# Booster_PA_PREAMP.net
KiCad netlist of a schematic drawn in Altium Designer
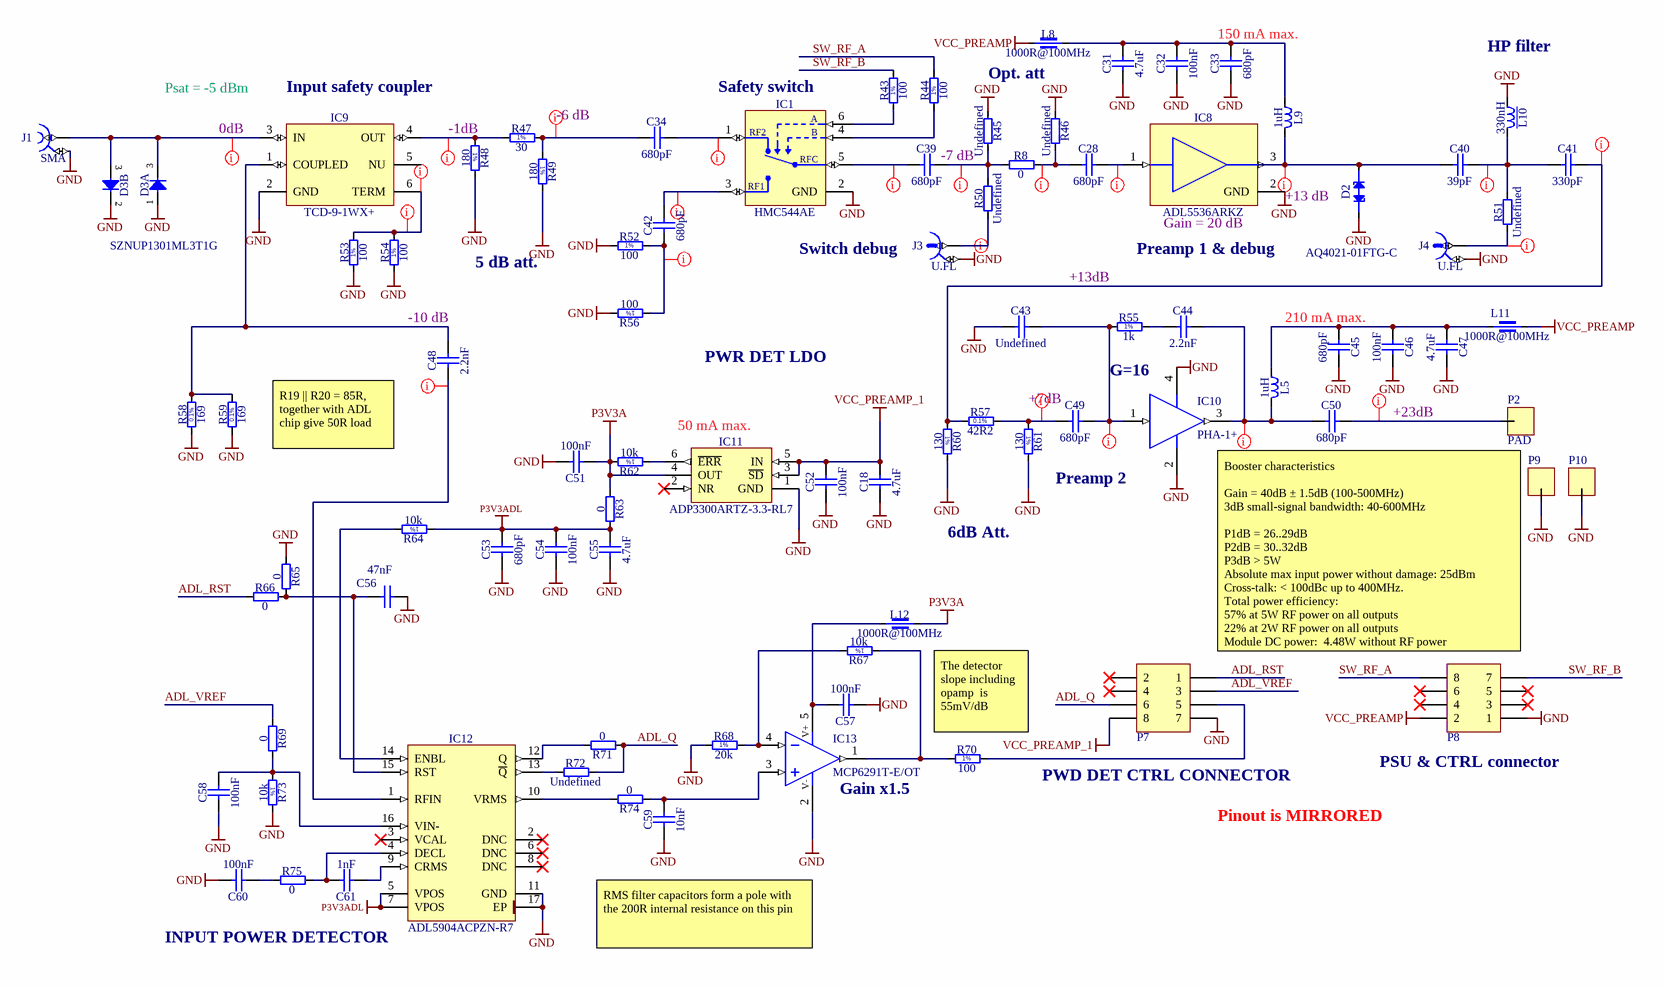
[diagram p0: Booster_PA_PREAMP.SchDoc]

(export (version "E")
  (design (tool "Eeschema 10.0.6"))
  (components
    (comp (ref "C18")
      (value "4.7uF")
      (footprint "CAPC1709X95N")
      (description "Non-polarised capacitor")
      (fields
        (field (name "MANUFACTURER") "GENERIC")
        (field (name "MANUFACTURER PART NUMBER") "CC0603_4.7UF_16V_10%_X5R")
        (field (name "AUTHOR") "CERN DEM JLC")
      )
      (libsource (lib "Capacitors") (part "Capacitor - non polarized"))
    )
    (comp (ref "C28")
      (value "680pF")
      (footprint "CAPC1608X87N")
      (description "Non-polarised capacitor")
      (fields
        (field (name "PART NUMBER") "CC0603_680PF_50V_5%_NP0")
        (field (name "VOLTAGE") "50V")
        (field (name "AUTHOR") "CERN DEM JLC")
      )
      (libsource (lib "Capacitors") (part "Capacitor - non polarized"))
    )
    (comp (ref "C31")
      (value "4.7uF")
      (footprint "CAPC1709X95N")
      (description "Non-polarised capacitor")
      (fields
        (field (name "MANUFACTURER") "GENERIC")
        (field (name "MANUFACTURER PART NUMBER") "CC0603_4.7UF_16V_10%_X5R")
        (field (name "AUTHOR") "CERN DEM JLC")
      )
      (libsource (lib "Capacitors") (part "Capacitor - non polarized"))
    )
    (comp (ref "C32")
      (value "100nF")
      (footprint "CAPC1608X87N")
      (description "Non-polarised capacitor")
      (fields
        (field (name "MANUFACTURER") "GENERIC")
        (field (name "MANUFACTURER PART NUMBER") "CC0603_100NF_50V_10%_X7R")
        (field (name "AUTHOR") "CERN DEM JLC")
      )
      (libsource (lib "Capacitors") (part "Capacitor - non polarized"))
    )
    (comp (ref "C33")
      (value "680pF")
      (footprint "CAPC1608X87N")
      (description "Non-polarised capacitor")
      (fields
        (field (name "PART NUMBER") "CC0603_680PF_50V_5%_NP0")
        (field (name "VOLTAGE") "50V")
        (field (name "AUTHOR") "CERN DEM JLC")
      )
      (libsource (lib "Capacitors") (part "Capacitor - non polarized"))
    )
    (comp (ref "C34")
      (value "680pF")
      (footprint "CAPC1608X87N")
      (description "Non-polarised capacitor")
      (fields
        (field (name "PART NUMBER") "CC0603_680PF_50V_5%_NP0")
        (field (name "VOLTAGE") "50V")
        (field (name "AUTHOR") "CERN DEM JLC")
      )
      (libsource (lib "Capacitors") (part "Capacitor - non polarized"))
    )
    (comp (ref "C39")
      (value "680pF")
      (footprint "CAPC1608X87N")
      (description "Non-polarised capacitor")
      (fields
        (field (name "PART NUMBER") "CC0603_680PF_50V_5%_NP0")
        (field (name "VOLTAGE") "50V")
        (field (name "AUTHOR") "CERN DEM JLC")
      )
      (libsource (lib "Capacitors") (part "Capacitor - non polarized"))
    )
    (comp (ref "C40")
      (value "39pF")
      (footprint "CAPC1608X87N")
      (description "Non-polarised capacitor")
      (fields
        (field (name "PART NUMBER") "CC0603_39PF_100V_1%_NP0")
        (field (name "VOLTAGE") "100V")
        (field (name "AUTHOR") "GK")
      )
      (libsource (lib "Passives_RC") (part "CC0603_39PF_50V_1%_NP0"))
    )
    (comp (ref "C41")
      (value "330pF")
      (footprint "CAPC1608X87N")
      (description "Non-polarised capacitor")
      (fields
        (field (name "MANUFACTURER") "GENERIC")
        (field (name "MANUFACTURER PART NUMBER") "CC0603_330PF_50V_1%_NP0")
        (field (name "AUTHOR") "CERN DEM MR")
      )
      (libsource (lib "Capacitors") (part "Capacitor - non polarized"))
    )
    (comp (ref "C42")
      (value "680pF")
      (footprint "CAPC1608X87N")
      (description "Non-polarised capacitor")
      (fields
        (field (name "PART NUMBER") "CC0603_680PF_50V_5%_NP0")
        (field (name "VOLTAGE") "50V")
        (field (name "AUTHOR") "CERN DEM JLC")
      )
      (libsource (lib "Capacitors") (part "Capacitor - non polarized"))
    )
    (comp (ref "C43")
      (value "Undefined")
      (footprint "CAPC1608X90N")
      (description "Non-polarised capacitor")
      (fields (field (name "PART NUMBER") "CC0603_NO-VALUE") (field (name "AUTHOR") "CERN DEM MR"))
      (libsource (lib "Capacitors") (part "Capacitor - non polarized"))
    )
    (comp (ref "C44")
      (value "2.2nF")
      (footprint "CAPC1608X87N")
      (description "Non-polarised capacitor")
      (fields
        (field (name "PART NUMBER") "CC0603_2.2NF_50V_5%_C0G")
        (field (name "VOLTAGE") "50V")
        (field (name "AUTHOR") "CERN DEM JMW")
      )
      (libsource (lib "Capacitors") (part "Capacitor - non polarized"))
    )
    (comp (ref "C45")
      (value "680pF")
      (footprint "CAPC1608X87N")
      (description "Non-polarised capacitor")
      (fields
        (field (name "MANUFACTURER") "GENERIC")
        (field (name "MANUFACTURER PART NUMBER") "CC0603_680PF_50V_5%_NP0")
        (field (name "AUTHOR") "CERN DEM JLC")
      )
      (libsource (lib "Capacitors") (part "Capacitor - non polarized"))
    )
    (comp (ref "C46")
      (value "100nF")
      (footprint "CAPC1608X87N")
      (description "Non-polarised capacitor")
      (fields
        (field (name "MANUFACTURER") "GENERIC")
        (field (name "MANUFACTURER PART NUMBER") "CC0603_100NF_50V_10%_X7R")
        (field (name "AUTHOR") "CERN DEM JLC")
      )
      (libsource (lib "Capacitors") (part "Capacitor - non polarized"))
    )
    (comp (ref "C47")
      (value "4.7uF")
      (footprint "CAPC1709X95N")
      (description "Non-polarised capacitor")
      (fields
        (field (name "MANUFACTURER") "GENERIC")
        (field (name "MANUFACTURER PART NUMBER") "CC0603_4.7UF_16V_10%_X5R")
        (field (name "AUTHOR") "CERN DEM JLC")
      )
      (libsource (lib "Capacitors") (part "Capacitor - non polarized"))
    )
    (comp (ref "C48")
      (value "2.2nF")
      (footprint "CAPC1608X87N")
      (description "Non-polarised capacitor")
      (fields
        (field (name "PART NUMBER") "CC0603_2.2NF_50V_5%_C0G")
        (field (name "VOLTAGE") "50V")
        (field (name "AUTHOR") "CERN DEM JMW")
      )
      (libsource (lib "Capacitors") (part "Capacitor - non polarized"))
    )
    (comp (ref "C49")
      (value "680pF")
      (footprint "CAPC1608X87N")
      (description "Non-polarised capacitor")
      (fields
        (field (name "MANUFACTURER") "GENERIC")
        (field (name "MANUFACTURER PART NUMBER") "CC0603_680PF_50V_5%_NP0")
        (field (name "AUTHOR") "CERN DEM JLC")
      )
      (libsource (lib "Capacitors") (part "Capacitor - non polarized"))
    )
    (comp (ref "C50")
      (value "680pF")
      (footprint "CAPC1608X87N")
      (description "Non-polarised capacitor")
      (fields
        (field (name "MANUFACTURER") "GENERIC")
        (field (name "MANUFACTURER PART NUMBER") "CC0603_680PF_50V_5%_NP0")
        (field (name "AUTHOR") "CERN DEM JLC")
      )
      (libsource (lib "Capacitors") (part "Capacitor - non polarized"))
    )
    (comp (ref "C51")
      (value "100nF")
      (footprint "CAPC1608X87N")
      (description "Non-polarised capacitor")
      (fields
        (field (name "MANUFACTURER") "GENERIC")
        (field (name "MANUFACTURER PART NUMBER") "CC0603_100NF_50V_10%_X7R")
        (field (name "AUTHOR") "CERN DEM JLC")
      )
      (libsource (lib "Capacitors") (part "Capacitor - non polarized"))
    )
    (comp (ref "C52")
      (value "100nF")
      (footprint "CAPC1608X87N")
      (description "Non-polarised capacitor")
      (fields
        (field (name "MANUFACTURER") "GENERIC")
        (field (name "MANUFACTURER PART NUMBER") "CC0603_100NF_50V_10%_X7R")
        (field (name "AUTHOR") "CERN DEM JLC")
      )
      (libsource (lib "Capacitors") (part "Capacitor - non polarized"))
    )
    (comp (ref "C53")
      (value "680pF")
      (footprint "CAPC1608X87N")
      (description "Non-polarised capacitor")
      (fields
        (field (name "MANUFACTURER") "GENERIC")
        (field (name "MANUFACTURER PART NUMBER") "CC0603_680PF_50V_5%_NP0")
        (field (name "AUTHOR") "CERN DEM JLC")
      )
      (libsource (lib "Capacitors") (part "Capacitor - non polarized"))
    )
    (comp (ref "C54")
      (value "100nF")
      (footprint "CAPC1608X87N")
      (description "Non-polarised capacitor")
      (fields
        (field (name "MANUFACTURER") "GENERIC")
        (field (name "MANUFACTURER PART NUMBER") "CC0603_100NF_50V_10%_X7R")
        (field (name "AUTHOR") "CERN DEM JLC")
      )
      (libsource (lib "Capacitors") (part "Capacitor - non polarized"))
    )
    (comp (ref "C55")
      (value "4.7uF")
      (footprint "CAPC1709X95N")
      (description "Non-polarised capacitor")
      (fields
        (field (name "MANUFACTURER") "GENERIC")
        (field (name "MANUFACTURER PART NUMBER") "CC0603_4.7UF_16V_10%_X5R")
        (field (name "AUTHOR") "CERN DEM JLC")
      )
      (libsource (lib "Capacitors") (part "Capacitor - non polarized"))
    )
    (comp (ref "C56")
      (value "47nF")
      (footprint "CAPC1608X87N")
      (description "Non-polarised capacitor")
      (fields
        (field (name "PART NUMBER") "CC0603_47NF_25V_10%_X7R")
        (field (name "VOLTAGE") "25V")
        (field (name "AUTHOR") "CERN DEM JLC")
      )
      (libsource (lib "Capacitors") (part "Capacitor - non polarized"))
    )
    (comp (ref "C57")
      (value "100nF")
      (footprint "CAPC1608X87N")
      (description "Non-polarised capacitor")
      (fields
        (field (name "MANUFACTURER") "GENERIC")
        (field (name "MANUFACTURER PART NUMBER") "CC0603_100NF_50V_10%_X7R")
        (field (name "AUTHOR") "CERN DEM JLC")
      )
      (libsource (lib "Capacitors") (part "Capacitor - non polarized"))
    )
    (comp (ref "C58")
      (value "100nF")
      (footprint "CAPC1608X87N")
      (description "Non-polarised capacitor")
      (fields
        (field (name "MANUFACTURER") "GENERIC")
        (field (name "MANUFACTURER PART NUMBER") "CC0603_100NF_50V_10%_X7R")
        (field (name "AUTHOR") "CERN DEM JLC")
      )
      (libsource (lib "Capacitors") (part "Capacitor - non polarized"))
    )
    (comp (ref "C59")
      (value "10nF")
      (footprint "CAPC1005X55N")
      (description "Non-polarised capacitor")
      (fields
        (field (name "MANUFACTURER") "GENERIC")
        (field (name "MANUFACTURER PART NUMBER") "CC0402_10NF_25V_10%_X7R")
        (field (name "AUTHOR") "CERN DEM JLC")
      )
      (libsource (lib "Capacitors") (part "Capacitor - non polarized"))
    )
    (comp (ref "C60")
      (value "100nF")
      (footprint "CAPC1608X87N")
      (description "Non-polarised capacitor")
      (fields
        (field (name "MANUFACTURER") "GENERIC")
        (field (name "MANUFACTURER PART NUMBER") "CC0603_100NF_50V_10%_X7R")
        (field (name "AUTHOR") "CERN DEM JLC")
      )
      (libsource (lib "Capacitors") (part "Capacitor - non polarized"))
    )
    (comp (ref "C61")
      (value "1nF")
      (footprint "CAPC1005X55N")
      (description "Non-polarised capacitor")
      (fields
        (field (name "PART NUMBER") "CC0402_1NF_50V_10%_X7R")
        (field (name "VOLTAGE") "50V")
        (field (name "AUTHOR") "CERN DEM JLC")
      )
      (libsource (lib "Capacitors") (part "Capacitor - non polarized"))
    )
    (comp (ref "D2")
      (value "AQ4021-01FTG-C")
      (footprint "SOD2513X114N")
      (description "6V Bi-directional,ESD Protection for Transient Voltage Suppressor Diode")
      (fields (field (name "VOLTAGE") "6V") (field (name "POWER") "450W") (field (name "AUTHOR") "GK"))
      (libsource (lib "Diodes") (part "D_TVS_AQ4021-01FTG-C"))
    )
    (comp (ref "D3")
      (value "SZNUP1301ML3T1G")
      (footprint "SOT95P240X110-3N")
      (description "Low Capacitance Diode Array for ESD Protection in a Single Data Line")
      (fields (field (name "VOLTAGE") "70V") (field (name "POWER") "215mA") (field (name "AUTHOR") "GK"))
      (libsource (lib "Diodes") (part "D_TVS_SZNUP1301ML3T1G"))
    )
    (comp (ref "IC1")
      (value "HMC544AE")
      (footprint "SOT95P280X145-6N")
      (description "GaAs MMIC T/R Switch DC - 4 GHz")
      (fields (field (name "MANUFACTURER") "ANALOG DEVICES") (field (name "AUTHOR") "CERN DEM MR"))
      (libsource (lib "ICs And Semiconductors") (part "HMC544AE"))
    )
    (comp (ref "IC8")
      (value "ADL5536ARKZ")
      (footprint "ANALOG-DEVICES_SOT-89(RK-3)")
      (description "20MHz to 1GHz IF Gain Block")
      (fields (field (name "MANUFACTURER") "ANALOG DEVICES") (field (name "AUTHOR") "CERN DEM BC"))
      (libsource (lib "ICs And Semiconductors") (part "ADL5536"))
    )
    (comp (ref "IC9")
      (value "TCD-9-1WX+")
      (footprint "MINI-CIRCUITS_DB1627")
      (description "50 Ohm, 5 To 2000MHz, Directional Coupler")
      (fields (field (name "MANUFACTURER") "MINI-CIRCUITS") (field (name "AUTHOR") "CERN DEM BC"))
      (libsource (lib "ICs And Semiconductors") (part "TCD-9-1W"))
    )
    (comp (ref "IC10")
      (value "PHA-1+")
      (footprint "MINI-CIRCUITS_DF782")
      (description "Monolithic Amplifier")
      (fields (field (name "MANUFACTURER") "MINI-CIRCUITS") (field (name "AUTHOR") "CERN DEM BC"))
      (libsource (lib "ICs And Semiconductors") (part "Monolithic Amplifier Type 1"))
    )
    (comp (ref "IC11")
      (value "ADP3300ARTZ-3.3-RL7")
      (footprint "SOT95P280X145-6N")
      (description "High Accuracy anyCAP® 50 mA Low Dropout Linear Regulator")
      (fields (field (name "MANUFACTURER") "ANALOG DEVICES") (field (name "AUTHOR") "CERN DEM JLC"))
      (libsource (lib "ICs And Semiconductors") (part "ADP3300ARTZ"))
    )
    (comp (ref "IC12")
      (value "ADL5904ACPZN-R7")
      (footprint "QFN50P300X300X80-17N-S175")
      (description "DC to 6 GHz, 45 dB TruPwr Detector With Envelope Threshold Detection")
      (fields (field (name "MANUFACTURER") "ANALOG DEVICES") (field (name "AUTHOR") "CERN DEM MR"))
      (libsource (lib "ICs And Semiconductors") (part "ADL5904"))
    )
    (comp (ref "IC13")
      (value "MCP6291T-E/OT")
      (footprint "SOT95P270X145-5N")
      (description "Operational Amplifier")
      (fields (field (name "MANUFACTURER") "MICROCHIP TECHNOLOGY") (field (name "AUTHOR") "CERN DEM BC"))
      (libsource (lib "ICs And Semiconductors") (part "Operational Amplifier Type7"))
    )
    (comp (ref "J1")
      (value "SMA")
      (footprint "LINK_CONSMA002-SMD-G")
      (fields
        (field (name "PART NUMBER") "LINK_CONSMA002-SMD-G")
        (field (name "MANUFACTURER") "LINK TECHNOLOGIES")
        (field (name "MANUFACTURER PART NUMBER") "CONSMA002-SMD-G")
        (field (name "AUTHOR") "CERN DEM BC")
      )
      (libsource (lib "Connectors") (part "Coax_1Female_1Shield"))
    )
    (comp (ref "J3")
      (value "U.FL")
      (footprint "HIROSE_U.FL-R-SMT-1(10)")
      (fields
        (field (name "PART NUMBER") "HIROSE_U.FL-R-SMT-1(10)")
        (field (name "MANUFACTURER") "HIROSE (HRS)")
        (field (name "MANUFACTURER PART NUMBER") "U.FL-R-SMT-1(10)")
        (field (name "AUTHOR") "CERN DEM JLC")
      )
      (libsource (lib "Connectors") (part "Coax_1Male_1Shield"))
    )
    (comp (ref "J4")
      (value "U.FL")
      (footprint "HIROSE_U.FL-R-SMT-1(10)")
      (fields
        (field (name "PART NUMBER") "HIROSE_U.FL-R-SMT-1(10)")
        (field (name "MANUFACTURER") "HIROSE (HRS)")
        (field (name "MANUFACTURER PART NUMBER") "U.FL-R-SMT-1(10)")
        (field (name "AUTHOR") "CERN DEM JLC")
      )
      (libsource (lib "Connectors") (part "Coax_1Male_1Shield"))
    )
    (comp (ref "L5")
      (value "1uH")
      (footprint "IND_ABRACON_AISC-1008")
      (description "Inductor")
      (fields
        (field (name "PART NUMBER") "IND_1UH_2%_ABRACON_AISC-1008")
        (field (name "POWER") "370mA")
        (field (name "AUTHOR") "CERN DEM BC")
      )
      (libsource (lib "Inductors & Transformers") (part "Inductor"))
    )
    (comp (ref "L8")
      (value "1000R@100MHz")
      (footprint "INDC1608X95N")
      (fields
        (field (name "MANUFACTURER") "MURATA")
        (field (name "MANUFACTURER PART NUMBER") "BLM18HE102SN1")
        (field (name "PART NUMBER") "IND0603_MURATA_BLM18HE102SN1")
        (field (name "AUTHOR") "CERN DEM JLC")
      )
      (libsource (lib "Inductors & Transformers") (part "Ferrite Bead"))
    )
    (comp (ref "L9")
      (value "1uH")
      (footprint "IND_ABRACON_AISC-1008")
      (description "Inductor")
      (fields
        (field (name "PART NUMBER") "IND_1UH_2%_ABRACON_AISC-1008")
        (field (name "POWER") "370mA")
        (field (name "AUTHOR") "CERN DEM BC")
      )
      (libsource (lib "Inductors & Transformers") (part "Inductor"))
    )
    (comp (ref "L10")
      (value "330nH")
      (footprint "IND_COILCRAFT_0603LS")
      (description "Inductor With Core")
      (fields
        (field (name "PART NUMBER") "IND_330NH_2%_COILCRAFT_0603LS")
        (field (name "POWER") "560mA")
        (field (name "AUTHOR") "CERN DEM BC")
      )
      (libsource (lib "Inductors & Transformers") (part "Inductor With Magnetic core"))
    )
    (comp (ref "L11")
      (value "1000R@100MHz")
      (footprint "INDC1608X95N")
      (fields
        (field (name "MANUFACTURER") "MURATA")
        (field (name "MANUFACTURER PART NUMBER") "BLM18HE102SN1")
        (field (name "PART NUMBER") "IND0603_MURATA_BLM18HE102SN1")
        (field (name "AUTHOR") "CERN DEM JLC")
      )
      (libsource (lib "Inductors & Transformers") (part "Ferrite Bead"))
    )
    (comp (ref "L12")
      (value "1000R@100MHz")
      (footprint "INDC1608X95N")
      (fields
        (field (name "MANUFACTURER") "MURATA")
        (field (name "MANUFACTURER PART NUMBER") "BLM18HE102SN1")
        (field (name "PART NUMBER") "IND0603_MURATA_BLM18HE102SN1")
        (field (name "AUTHOR") "CERN DEM JLC")
      )
      (libsource (lib "Inductors & Transformers") (part "Ferrite Bead"))
    )
    (comp (ref "P2")
      (value "PAD")
      (footprint "PAD_2x3_rect")
      (libsource (lib "elementy_stykowe") (part "PAD"))
    )
    (comp (ref "P7")
      (value "HDR2X4")
      (footprint "HDR2X4_SMD")
      (description "Header, 4-Pin, Dual Row")
      (libsource (lib "onyks") (part "HDR2X4"))
    )
    (comp (ref "P8")
      (value "HDR2X4")
      (footprint "HDR2X4_SMD")
      (description "Header, 4-Pin, Dual Row")
      (libsource (lib "") (part "HDR2X4_1"))
    )
    (comp (ref "P9") (value "PAD") (footprint "PAD_2x3_rect") (libsource (lib "") (part "PAD_1")))
    (comp (ref "P10") (value "PAD") (footprint "PAD_2x3_rect") (libsource (lib "") (part "PAD_1")))
    (comp (ref "R8")
      (value "0")
      (footprint "RESC1005X40N")
      (description "Resistor")
      (fields
        (field (name "MANUFACTURER") "GENERIC")
        (field (name "MANUFACTURER PART NUMBER") "R0402_0R_JUMPER")
        (field (name "AUTHOR") "CERN DEM JLC")
      )
      (libsource (lib "Resistors") (part "Resistor"))
    )
    (comp (ref "R43")
      (value "100")
      (footprint "RESC1608X55N")
      (description "Resistor - 1%")
      (fields
        (field (name "MANUFACTURER") "GENERIC")
        (field (name "MANUFACTURER PART NUMBER") "R0603_100R_1%_0.1W_100PPM")
        (field (name "AUTHOR") "CERN DEM JLC")
      )
      (libsource (lib "Resistors") (part "Resistor - 1%"))
    )
    (comp (ref "R44")
      (value "100")
      (footprint "RESC1608X55N")
      (description "Resistor - 1%")
      (fields
        (field (name "MANUFACTURER") "GENERIC")
        (field (name "MANUFACTURER PART NUMBER") "R0603_100R_1%_0.1W_100PPM")
        (field (name "AUTHOR") "CERN DEM JLC")
      )
      (libsource (lib "Resistors") (part "Resistor - 1%"))
    )
    (comp (ref "R45")
      (value "Undefined")
      (footprint "RESC1608X55N")
      (description "Resistor")
      (fields
        (field (name "MANUFACTURER PART NUMBER") "R0603_NO-VALUE")
        (field (name "AUTHOR") "CERN DEM JLC")
      )
      (libsource (lib "Resistors") (part "Resistor"))
    )
    (comp (ref "R46")
      (value "Undefined")
      (footprint "RESC1608X55N")
      (description "Resistor")
      (fields
        (field (name "MANUFACTURER PART NUMBER") "R0603_NO-VALUE")
        (field (name "AUTHOR") "CERN DEM JLC")
      )
      (libsource (lib "Resistors") (part "Resistor"))
    )
    (comp (ref "R47")
      (value "30")
      (footprint "RESC1608X55N")
      (description "Resistor - 1%")
      (fields
        (field (name "PART NUMBER") "R0603_30R_1%_0.1W_100PPM")
        (field (name "POWER") "0.1W")
        (field (name "AUTHOR") "CERN DEM JLC")
      )
      (libsource (lib "Resistors") (part "Resistor - 1%"))
    )
    (comp (ref "R48")
      (value "180")
      (footprint "RESC1608X55N")
      (description "Resistor - 1%")
      (fields
        (field (name "MANUFACTURER") "GENERIC")
        (field (name "MANUFACTURER PART NUMBER") "R0603_180R_1%_0.1W_100PPM")
        (field (name "AUTHOR") "CERN DEM JLC")
      )
      (libsource (lib "Resistors") (part "Resistor - 1%"))
    )
    (comp (ref "R49")
      (value "180")
      (footprint "RESC1608X55N")
      (description "Resistor - 1%")
      (fields
        (field (name "MANUFACTURER") "GENERIC")
        (field (name "MANUFACTURER PART NUMBER") "R0603_180R_1%_0.1W_100PPM")
        (field (name "AUTHOR") "CERN DEM JLC")
      )
      (libsource (lib "Resistors") (part "Resistor - 1%"))
    )
    (comp (ref "R50")
      (value "Undefined")
      (footprint "RESC1608X55N")
      (description "Resistor")
      (fields
        (field (name "MANUFACTURER PART NUMBER") "R0603_NO-VALUE")
        (field (name "AUTHOR") "CERN DEM JLC")
      )
      (libsource (lib "Resistors") (part "Resistor"))
    )
    (comp (ref "R51")
      (value "Undefined")
      (footprint "RESC1608X55N")
      (description "Resistor")
      (fields
        (field (name "MANUFACTURER PART NUMBER") "R0603_NO-VALUE")
        (field (name "AUTHOR") "CERN DEM JLC")
      )
      (libsource (lib "Resistors") (part "Resistor"))
    )
    (comp (ref "R52")
      (value "100")
      (footprint "RESC1608X55N")
      (description "Resistor - 1%")
      (fields
        (field (name "MANUFACTURER") "GENERIC")
        (field (name "MANUFACTURER PART NUMBER") "R0603_100R_1%_0.1W_100PPM")
        (field (name "AUTHOR") "CERN DEM JLC")
      )
      (libsource (lib "Resistors") (part "Resistor - 1%"))
    )
    (comp (ref "R53")
      (value "100")
      (footprint "RESC1608X55N")
      (description "Resistor - 1%")
      (fields
        (field (name "MANUFACTURER") "GENERIC")
        (field (name "MANUFACTURER PART NUMBER") "R0603_100R_1%_0.1W_100PPM")
        (field (name "AUTHOR") "CERN DEM JLC")
      )
      (libsource (lib "Resistors") (part "Resistor - 1%"))
    )
    (comp (ref "R54")
      (value "100")
      (footprint "RESC1608X55N")
      (description "Resistor - 1%")
      (fields
        (field (name "MANUFACTURER") "GENERIC")
        (field (name "MANUFACTURER PART NUMBER") "R0603_100R_1%_0.1W_100PPM")
        (field (name "AUTHOR") "CERN DEM JLC")
      )
      (libsource (lib "Resistors") (part "Resistor - 1%"))
    )
    (comp (ref "R55")
      (value "1k")
      (footprint "RESC1608X55N")
      (description "Resistor - 1%")
      (fields
        (field (name "MANUFACTURER") "GENERIC")
        (field (name "MANUFACTURER PART NUMBER") "R0603_1K_1%_0.1W_100PPM")
        (field (name "AUTHOR") "CERN DEM JLC")
      )
      (libsource (lib "Resistors") (part "Resistor - 1%"))
    )
    (comp (ref "R56")
      (value "100")
      (footprint "RESC1608X55N")
      (description "Resistor - 1%")
      (fields
        (field (name "MANUFACTURER") "GENERIC")
        (field (name "MANUFACTURER PART NUMBER") "R0603_100R_1%_0.1W_100PPM")
        (field (name "AUTHOR") "CERN DEM JLC")
      )
      (libsource (lib "Resistors") (part "Resistor - 1%"))
    )
    (comp (ref "R57")
      (value "42R2")
      (footprint "RESC1608X55N")
      (description "Resistor - 0.1%")
      (fields
        (field (name "PART NUMBER") "R0603_42R2_0.1%_0.063W_10PPM")
        (field (name "POWER") "0.063W")
        (field (name "AUTHOR") "CERN DEM JLC")
      )
      (libsource (lib "Resistors") (part "Resistor - 0.1%"))
    )
    (comp (ref "R58")
      (value "169")
      (footprint "RESC1608X55N")
      (description "Resistor - 0.1%")
      (fields
        (field (name "PART NUMBER") "R0603_169R_0.1%_0.063W_10PPM")
        (field (name "POWER") "0.063W")
        (field (name "AUTHOR") "CERN DEM JLC")
      )
      (libsource (lib "Resistors") (part "Resistor - 0.1%"))
    )
    (comp (ref "R59")
      (value "169")
      (footprint "RESC1608X55N")
      (description "Resistor - 0.1%")
      (fields
        (field (name "PART NUMBER") "R0603_169R_0.1%_0.063W_10PPM")
        (field (name "POWER") "0.063W")
        (field (name "AUTHOR") "CERN DEM JLC")
      )
      (libsource (lib "Resistors") (part "Resistor - 0.1%"))
    )
    (comp (ref "R60")
      (value "130")
      (footprint "RESC1608X55N")
      (description "Resistor - 1%")
      (fields
        (field (name "MANUFACTURER") "GENERIC")
        (field (name "MANUFACTURER PART NUMBER") "R0603_130R_1%_0.1W_100PPM")
        (field (name "AUTHOR") "CERN DEM JLC")
      )
      (libsource (lib "Resistors") (part "Resistor - 1%"))
    )
    (comp (ref "R61")
      (value "130")
      (footprint "RESC1608X55N")
      (description "Resistor - 1%")
      (fields
        (field (name "MANUFACTURER") "GENERIC")
        (field (name "MANUFACTURER PART NUMBER") "R0603_130R_1%_0.1W_100PPM")
        (field (name "AUTHOR") "CERN DEM JLC")
      )
      (libsource (lib "Resistors") (part "Resistor - 1%"))
    )
    (comp (ref "R62")
      (value "10k")
      (footprint "RESC1005X40N")
      (description "Resistor - 1%")
      (fields
        (field (name "MANUFACTURER") "GENERIC")
        (field (name "MANUFACTURER PART NUMBER") "R0402_10K_1%_0.0625W_100PPM")
        (field (name "AUTHOR") "CERN DEM JLC")
      )
      (libsource (lib "Resistors") (part "Resistor - 1%"))
    )
    (comp (ref "R63")
      (value "0")
      (footprint "RESC1005X40N")
      (description "Resistor")
      (fields
        (field (name "MANUFACTURER") "GENERIC")
        (field (name "MANUFACTURER PART NUMBER") "R0402_0R_JUMPER")
        (field (name "AUTHOR") "CERN DEM JLC")
      )
      (libsource (lib "Resistors") (part "Resistor"))
    )
    (comp (ref "R64")
      (value "10k")
      (footprint "RESC1005X40N")
      (description "Resistor - 1%")
      (fields
        (field (name "MANUFACTURER") "GENERIC")
        (field (name "MANUFACTURER PART NUMBER") "R0402_10K_1%_0.0625W_100PPM")
        (field (name "AUTHOR") "CERN DEM JLC")
      )
      (libsource (lib "Resistors") (part "Resistor - 1%"))
    )
    (comp (ref "R65")
      (value "0")
      (footprint "RESC1005X40N")
      (description "Resistor")
      (fields
        (field (name "MANUFACTURER") "GENERIC")
        (field (name "MANUFACTURER PART NUMBER") "R0402_0R_JUMPER")
        (field (name "AUTHOR") "CERN DEM JLC")
      )
      (libsource (lib "Resistors") (part "Resistor"))
    )
    (comp (ref "R66")
      (value "0")
      (footprint "RESC1005X40N")
      (description "Resistor")
      (fields
        (field (name "MANUFACTURER") "GENERIC")
        (field (name "MANUFACTURER PART NUMBER") "R0402_0R_JUMPER")
        (field (name "AUTHOR") "CERN DEM JLC")
      )
      (libsource (lib "Resistors") (part "Resistor"))
    )
    (comp (ref "R67")
      (value "10k")
      (footprint "RESC1005X40N")
      (description "Resistor - 1%")
      (fields
        (field (name "MANUFACTURER") "GENERIC")
        (field (name "MANUFACTURER PART NUMBER") "R0402_10K_1%_0.0625W_100PPM")
        (field (name "AUTHOR") "CERN DEM JLC")
      )
      (libsource (lib "Resistors") (part "Resistor - 1%"))
    )
    (comp (ref "R68")
      (value "20k")
      (footprint "RESC1608X55N")
      (description "Resistor - 1%")
      (fields
        (field (name "PART NUMBER") "R0603_20K_1%_0.1W_100PPM")
        (field (name "POWER") "0.1W")
        (field (name "AUTHOR") "CERN DEM JLC")
      )
      (libsource (lib "Resistors") (part "Resistor - 1%"))
    )
    (comp (ref "R69")
      (value "0")
      (footprint "RESC1005X40N")
      (description "Resistor")
      (fields
        (field (name "MANUFACTURER") "GENERIC")
        (field (name "MANUFACTURER PART NUMBER") "R0402_0R_JUMPER")
        (field (name "AUTHOR") "CERN DEM JLC")
      )
      (libsource (lib "Resistors") (part "Resistor"))
    )
    (comp (ref "R70")
      (value "100")
      (footprint "RESC1608X55N")
      (description "Resistor - 1%")
      (fields
        (field (name "MANUFACTURER") "GENERIC")
        (field (name "MANUFACTURER PART NUMBER") "R0603_100R_1%_0.1W_100PPM")
        (field (name "AUTHOR") "CERN DEM JLC")
      )
      (libsource (lib "Resistors") (part "Resistor - 1%"))
    )
    (comp (ref "R71")
      (value "0")
      (footprint "RESC1005X40N")
      (description "Resistor")
      (fields
        (field (name "MANUFACTURER") "GENERIC")
        (field (name "MANUFACTURER PART NUMBER") "R0402_0R_JUMPER")
        (field (name "AUTHOR") "CERN DEM JLC")
      )
      (libsource (lib "Resistors") (part "Resistor"))
    )
    (comp (ref "R72")
      (value "Undefined")
      (footprint "RESC1608X55N")
      (description "Resistor")
      (fields
        (field (name "MANUFACTURER PART NUMBER") "R0603_NO-VALUE")
        (field (name "AUTHOR") "CERN DEM JLC")
      )
      (libsource (lib "Resistors") (part "Resistor"))
    )
    (comp (ref "R73")
      (value "10k")
      (footprint "RESC1005X40N")
      (description "Resistor - 1%")
      (fields
        (field (name "MANUFACTURER") "GENERIC")
        (field (name "MANUFACTURER PART NUMBER") "R0402_10K_1%_0.0625W_100PPM")
        (field (name "AUTHOR") "CERN DEM JLC")
      )
      (libsource (lib "Resistors") (part "Resistor - 1%"))
    )
    (comp (ref "R74")
      (value "0")
      (footprint "RESC1005X40N")
      (description "Resistor")
      (fields
        (field (name "MANUFACTURER") "GENERIC")
        (field (name "MANUFACTURER PART NUMBER") "R0402_0R_JUMPER")
        (field (name "AUTHOR") "CERN DEM JLC")
      )
      (libsource (lib "Resistors") (part "Resistor"))
    )
    (comp (ref "R75")
      (value "0")
      (footprint "RESC1005X40N")
      (description "Resistor")
      (fields
        (field (name "MANUFACTURER") "GENERIC")
        (field (name "MANUFACTURER PART NUMBER") "R0402_0R_JUMPER")
        (field (name "AUTHOR") "CERN DEM JLC")
      )
      (libsource (lib "Resistors") (part "Resistor"))
    )
  )
  (nets
    (net (code "1") (name "/ADL_Q") (class "Default")
      (node (ref "P7") (pin "6") (pinfunction "6_6") (pintype "passive"))
      (node (ref "R71") (pin "1") (pinfunction "1_1") (pintype "passive"))
      (node (ref "R72") (pin "2") (pinfunction "2_2") (pintype "passive"))
    )
    (net (code "2") (name "/ADL_RST") (class "Default")
      (node (ref "P7") (pin "1") (pinfunction "1_1") (pintype "passive"))
      (node (ref "R66") (pin "1") (pinfunction "1_1") (pintype "passive"))
    )
    (net (code "3") (name "/ADL_VREF") (class "Default")
      (node (ref "P7") (pin "3") (pinfunction "3_3") (pintype "passive"))
      (node (ref "R69") (pin "1") (pinfunction "1_1") (pintype "passive"))
    )
    (net (code "4") (name "/SW_RF_A") (class "Default")
      (node (ref "P8") (pin "8") (pinfunction "8_8") (pintype "passive"))
      (node (ref "R44") (pin "2") (pinfunction "2_2") (pintype "passive"))
    )
    (net (code "5") (name "/SW_RF_B") (class "Default")
      (node (ref "P8") (pin "7") (pinfunction "7_7") (pintype "passive"))
      (node (ref "R43") (pin "2") (pinfunction "2_2") (pintype "passive"))
    )
    (net (code "6") (name "GND") (class "Default")
      (node (ref "C18") (pin "1") (pinfunction "1_1") (pintype "passive"))
      (node (ref "C31") (pin "1") (pinfunction "1_1") (pintype "passive"))
      (node (ref "C32") (pin "1") (pinfunction "1_1") (pintype "passive"))
      (node (ref "C33") (pin "1") (pinfunction "1_1") (pintype "passive"))
      (node (ref "C43") (pin "1") (pinfunction "1_1") (pintype "passive"))
      (node (ref "C45") (pin "1") (pinfunction "1_1") (pintype "passive"))
      (node (ref "C46") (pin "1") (pinfunction "1_1") (pintype "passive"))
      (node (ref "C47") (pin "1") (pinfunction "1_1") (pintype "passive"))
      (node (ref "C51") (pin "2") (pinfunction "2_2") (pintype "passive"))
      (node (ref "C52") (pin "1") (pinfunction "1_1") (pintype "passive"))
      (node (ref "C53") (pin "1") (pinfunction "1_1") (pintype "passive"))
      (node (ref "C54") (pin "1") (pinfunction "1_1") (pintype "passive"))
      (node (ref "C55") (pin "1") (pinfunction "1_1") (pintype "passive"))
      (node (ref "C56") (pin "2") (pinfunction "2_2") (pintype "passive"))
      (node (ref "C57") (pin "1") (pinfunction "1_1") (pintype "passive"))
      (node (ref "C58") (pin "1") (pinfunction "1_1") (pintype "passive"))
      (node (ref "C59") (pin "1") (pinfunction "1_1") (pintype "passive"))
      (node (ref "C60") (pin "2") (pinfunction "2_2") (pintype "passive"))
      (node (ref "D2") (pin "1") (pinfunction "C_1") (pintype "passive"))
      (node (ref "D3") (pin "1") (pinfunction "A_1") (pintype "passive"))
      (node (ref "D3") (pin "2") (pinfunction "C_2") (pintype "passive"))
      (node (ref "IC1") (pin "2") (pinfunction "GND_2") (pintype "power_in"))
      (node (ref "IC10") (pin "2") (pinfunction "GND_2") (pintype "power_in"))
      (node (ref "IC10") (pin "4") (pinfunction "GND_4") (pintype "power_in"))
      (node (ref "IC11") (pin "1") (pinfunction "GND_1") (pintype "power_in"))
      (node (ref "IC12") (pin "11") (pinfunction "GND_11") (pintype "power_in"))
      (node (ref "IC12") (pin "17") (pinfunction "EP_17") (pintype "power_in"))
      (node (ref "IC13") (pin "2") (pinfunction "V-_2") (pintype "power_in"))
      (node (ref "IC8") (pin "2") (pinfunction "GND_2") (pintype "power_in"))
      (node (ref "IC9") (pin "2") (pinfunction "GND_2") (pintype "power_in"))
      (node (ref "J1") (pin "2") (pinfunction "2_2") (pintype "bidirectional"))
      (node (ref "J3") (pin "2") (pinfunction "2_2") (pintype "bidirectional"))
      (node (ref "J4") (pin "2") (pinfunction "2_2") (pintype "bidirectional"))
      (node (ref "L10") (pin "1") (pinfunction "1_1") (pintype "passive"))
      (node (ref "P10") (pin "1") (pinfunction "1_1") (pintype "passive"))
      (node (ref "P7") (pin "7") (pinfunction "7_7") (pintype "passive"))
      (node (ref "P8") (pin "1") (pinfunction "1_1") (pintype "passive"))
      (node (ref "P9") (pin "1") (pinfunction "1_1") (pintype "passive"))
      (node (ref "R45") (pin "1") (pinfunction "1_1") (pintype "passive"))
      (node (ref "R46") (pin "1") (pinfunction "1_1") (pintype "passive"))
      (node (ref "R48") (pin "2") (pinfunction "2_2") (pintype "passive"))
      (node (ref "R49") (pin "2") (pinfunction "2_2") (pintype "passive"))
      (node (ref "R52") (pin "1") (pinfunction "1_1") (pintype "passive"))
      (node (ref "R53") (pin "1") (pinfunction "1_1") (pintype "passive"))
      (node (ref "R54") (pin "1") (pinfunction "1_1") (pintype "passive"))
      (node (ref "R56") (pin "2") (pinfunction "2_2") (pintype "passive"))
      (node (ref "R58") (pin "1") (pinfunction "1_1") (pintype "passive"))
      (node (ref "R59") (pin "1") (pinfunction "1_1") (pintype "passive"))
      (node (ref "R60") (pin "2") (pinfunction "2_2") (pintype "passive"))
      (node (ref "R61") (pin "2") (pinfunction "2_2") (pintype "passive"))
      (node (ref "R65") (pin "1") (pinfunction "1_1") (pintype "passive"))
      (node (ref "R68") (pin "1") (pinfunction "1_1") (pintype "passive"))
      (node (ref "R73") (pin "2") (pinfunction "2_2") (pintype "passive"))
    )
    (net (code "7") (name "Net-(C28-Pad1)") (class "Default")
      (node (ref "C28") (pin "1") (pinfunction "1_1") (pintype "passive"))
      (node (ref "R46") (pin "2") (pinfunction "2_2") (pintype "passive"))
      (node (ref "R8") (pin "2") (pinfunction "2_2") (pintype "passive"))
    )
    (net (code "8") (name "Net-(C31-Pad2)") (class "Default")
      (node (ref "C31") (pin "2") (pinfunction "2_2") (pintype "passive"))
      (node (ref "C32") (pin "2") (pinfunction "2_2") (pintype "passive"))
      (node (ref "C33") (pin "2") (pinfunction "2_2") (pintype "passive"))
      (node (ref "L8") (pin "2") (pinfunction "2_2") (pintype "passive"))
      (node (ref "L9") (pin "1") (pinfunction "1_1") (pintype "passive"))
    )
    (net (code "9") (name "Net-(C34-Pad1)") (class "Default")
      (node (ref "C34") (pin "1") (pinfunction "1_1") (pintype "passive"))
      (node (ref "R47") (pin "2") (pinfunction "2_2") (pintype "passive"))
      (node (ref "R49") (pin "1") (pinfunction "1_1") (pintype "passive"))
    )
    (net (code "10") (name "Net-(C39-Pad2)") (class "Default")
      (node (ref "C39") (pin "2") (pinfunction "2_2") (pintype "passive"))
      (node (ref "R45") (pin "2") (pinfunction "2_2") (pintype "passive"))
      (node (ref "R50") (pin "2") (pinfunction "2_2") (pintype "passive"))
      (node (ref "R8") (pin "1") (pinfunction "1_1") (pintype "passive"))
    )
    (net (code "11") (name "Net-(C40-Pad2)") (class "Default")
      (node (ref "C40") (pin "2") (pinfunction "2_2") (pintype "passive"))
      (node (ref "C41") (pin "1") (pinfunction "1_1") (pintype "passive"))
      (node (ref "L10") (pin "2") (pinfunction "2_2") (pintype "passive"))
      (node (ref "R51") (pin "2") (pinfunction "2_2") (pintype "passive"))
    )
    (net (code "12") (name "Net-(C41-Pad2)") (class "Default")
      (node (ref "C41") (pin "2") (pinfunction "2_2") (pintype "passive"))
      (node (ref "R57") (pin "1") (pinfunction "1_1") (pintype "passive"))
      (node (ref "R60") (pin "1") (pinfunction "1_1") (pintype "passive"))
    )
    (net (code "13") (name "Net-(C42-Pad1)") (class "Default")
      (node (ref "C42") (pin "1") (pinfunction "1_1") (pintype "passive"))
      (node (ref "R52") (pin "2") (pinfunction "2_2") (pintype "passive"))
      (node (ref "R56") (pin "1") (pinfunction "1_1") (pintype "passive"))
    )
    (net (code "14") (name "Net-(C44-Pad1)") (class "Default")
      (node (ref "C44") (pin "1") (pinfunction "1_1") (pintype "passive"))
      (node (ref "R55") (pin "2") (pinfunction "2_2") (pintype "passive"))
    )
    (net (code "15") (name "Net-(C45-Pad2)") (class "Default")
      (node (ref "C45") (pin "2") (pinfunction "2_2") (pintype "passive"))
      (node (ref "C46") (pin "2") (pinfunction "2_2") (pintype "passive"))
      (node (ref "C47") (pin "2") (pinfunction "2_2") (pintype "passive"))
      (node (ref "L11") (pin "1") (pinfunction "1_1") (pintype "passive"))
      (node (ref "L5") (pin "1") (pinfunction "1_1") (pintype "passive"))
    )
    (net (code "16") (name "Net-(C49-Pad1)") (class "Default")
      (node (ref "C49") (pin "1") (pinfunction "1_1") (pintype "passive"))
      (node (ref "R57") (pin "2") (pinfunction "2_2") (pintype "passive"))
      (node (ref "R61") (pin "1") (pinfunction "1_1") (pintype "passive"))
    )
    (net (code "17") (name "Net-(C50-Pad2)") (class "Default")
      (node (ref "C50") (pin "2") (pinfunction "2_2") (pintype "passive"))
      (node (ref "P2") (pin "1") (pinfunction "1_1") (pintype "passive"))
    )
    (net (code "18") (name "Net-(C60-Pad1)") (class "Default")
      (node (ref "C60") (pin "1") (pinfunction "1_1") (pintype "passive"))
      (node (ref "R75") (pin "1") (pinfunction "1_1") (pintype "passive"))
    )
    (net (code "19") (name "Net-(D2-A)") (class "Default")
      (node (ref "C40") (pin "1") (pinfunction "1_1") (pintype "passive"))
      (node (ref "D2") (pin "2") (pinfunction "A_2") (pintype "passive"))
      (node (ref "IC8") (pin "3") (pinfunction "RFOUT_3") (pintype "output"))
      (node (ref "L9") (pin "2") (pinfunction "2_2") (pintype "passive"))
    )
    (net (code "20") (name "Net-(D3A-COMAC)") (class "Default")
      (node (ref "D3") (pin "3") (pinfunction "COMAC_3") (pintype "passive"))
      (node (ref "IC9") (pin "3") (pinfunction "IN_3") (pintype "bidirectional"))
      (node (ref "J1") (pin "1") (pinfunction "1_1") (pintype "bidirectional"))
    )
    (net (code "21") (name "Net-(IC1-A)") (class "Default")
      (node (ref "IC1") (pin "6") (pinfunction "A_6") (pintype "input"))
      (node (ref "R43") (pin "1") (pinfunction "1_1") (pintype "passive"))
    )
    (net (code "22") (name "Net-(IC1-B)") (class "Default")
      (node (ref "IC1") (pin "4") (pinfunction "B_4") (pintype "input"))
      (node (ref "R44") (pin "1") (pinfunction "1_1") (pintype "passive"))
    )
    (net (code "23") (name "Net-(IC1-RF1)") (class "Default")
      (node (ref "C42") (pin "2") (pinfunction "2_2") (pintype "passive"))
      (node (ref "IC1") (pin "3") (pinfunction "RF1_3") (pintype "bidirectional"))
    )
    (net (code "24") (name "Net-(IC1-RF2)") (class "Default")
      (node (ref "C34") (pin "2") (pinfunction "2_2") (pintype "passive"))
      (node (ref "IC1") (pin "1") (pinfunction "RF2_1") (pintype "bidirectional"))
    )
    (net (code "25") (name "Net-(IC1-RFC)") (class "Default")
      (node (ref "C39") (pin "1") (pinfunction "1_1") (pintype "passive"))
      (node (ref "IC1") (pin "5") (pinfunction "RFC_5") (pintype "bidirectional"))
    )
    (net (code "26") (name "Net-(IC8-RFIN)") (class "Default")
      (node (ref "C28") (pin "2") (pinfunction "2_2") (pintype "passive"))
      (node (ref "IC8") (pin "1") (pinfunction "RFIN_1") (pintype "input"))
    )
    (net (code "27") (name "Net-(IC9-COUPLED)") (class "Default")
      (node (ref "C48") (pin "2") (pinfunction "2_2") (pintype "passive"))
      (node (ref "IC9") (pin "1") (pinfunction "COUPLED_1") (pintype "bidirectional"))
      (node (ref "R58") (pin "2") (pinfunction "2_2") (pintype "passive"))
      (node (ref "R59") (pin "2") (pinfunction "2_2") (pintype "passive"))
    )
    (net (code "28") (name "Net-(IC9-OUT)") (class "Default")
      (node (ref "IC9") (pin "4") (pinfunction "OUT_4") (pintype "bidirectional"))
      (node (ref "R47") (pin "1") (pinfunction "1_1") (pintype "passive"))
      (node (ref "R48") (pin "1") (pinfunction "1_1") (pintype "passive"))
    )
    (net (code "29") (name "Net-(IC9-TERM)") (class "Default")
      (node (ref "IC9") (pin "6") (pinfunction "TERM_6") (pintype "passive"))
      (node (ref "R53") (pin "2") (pinfunction "2_2") (pintype "passive"))
      (node (ref "R54") (pin "2") (pinfunction "2_2") (pintype "passive"))
    )
    (net (code "30") (name "Net-(IC10-RF_IN)") (class "Default")
      (node (ref "C43") (pin "2") (pinfunction "2_2") (pintype "passive"))
      (node (ref "C49") (pin "2") (pinfunction "2_2") (pintype "passive"))
      (node (ref "IC10") (pin "1") (pinfunction "RF_IN_1") (pintype "input"))
      (node (ref "R55") (pin "1") (pinfunction "1_1") (pintype "passive"))
    )
    (net (code "31") (name "Net-(IC10-RF_OUT)") (class "Default")
      (node (ref "C44") (pin "2") (pinfunction "2_2") (pintype "passive"))
      (node (ref "C50") (pin "1") (pinfunction "1_1") (pintype "passive"))
      (node (ref "IC10") (pin "3") (pinfunction "RF_OUT_3") (pintype "output"))
      (node (ref "L5") (pin "2") (pinfunction "2_2") (pintype "passive"))
    )
    (net (code "32") (name "Net-(IC11-~{ERR})") (class "Default")
      (node (ref "IC11") (pin "6") (pinfunction "~{ERR}_6") (pintype "output"))
      (node (ref "R62") (pin "1") (pinfunction "1_1") (pintype "passive"))
    )
    (net (code "33") (name "Net-(IC12-CRMS)") (class "Default")
      (node (ref "C61") (pin "1") (pinfunction "1_1") (pintype "passive"))
      (node (ref "IC12") (pin "9") (pinfunction "CRMS_9") (pintype "input"))
    )
    (net (code "34") (name "Net-(IC12-DECL)") (class "Default")
      (node (ref "C61") (pin "2") (pinfunction "2_2") (pintype "passive"))
      (node (ref "IC12") (pin "4") (pinfunction "DECL_4") (pintype "input"))
      (node (ref "R75") (pin "2") (pinfunction "2_2") (pintype "passive"))
    )
    (net (code "35") (name "Net-(IC12-ENBL)") (class "Default")
      (node (ref "IC12") (pin "14") (pinfunction "ENBL_14") (pintype "input"))
      (node (ref "R64") (pin "2") (pinfunction "2_2") (pintype "passive"))
    )
    (net (code "36") (name "Net-(IC12-Q)") (class "Default")
      (node (ref "IC12") (pin "12") (pinfunction "Q_12") (pintype "output"))
      (node (ref "R71") (pin "2") (pinfunction "2_2") (pintype "passive"))
    )
    (net (code "37") (name "Net-(IC12-RFIN)") (class "Default")
      (node (ref "C48") (pin "1") (pinfunction "1_1") (pintype "passive"))
      (node (ref "IC12") (pin "1") (pinfunction "RFIN_1") (pintype "input"))
    )
    (net (code "38") (name "Net-(IC12-RST)") (class "Default")
      (node (ref "C56") (pin "1") (pinfunction "1_1") (pintype "passive"))
      (node (ref "IC12") (pin "15") (pinfunction "RST_15") (pintype "input"))
      (node (ref "R65") (pin "2") (pinfunction "2_2") (pintype "passive"))
      (node (ref "R66") (pin "2") (pinfunction "2_2") (pintype "passive"))
    )
    (net (code "39") (name "Net-(IC12-VIN-)") (class "Default")
      (node (ref "C58") (pin "2") (pinfunction "2_2") (pintype "passive"))
      (node (ref "IC12") (pin "16") (pinfunction "VIN-_16") (pintype "input"))
      (node (ref "R69") (pin "2") (pinfunction "2_2") (pintype "passive"))
      (node (ref "R73") (pin "1") (pinfunction "1_1") (pintype "passive"))
    )
    (net (code "40") (name "Net-(IC12-VRMS)") (class "Default")
      (node (ref "IC12") (pin "10") (pinfunction "VRMS_10") (pintype "output"))
      (node (ref "R74") (pin "2") (pinfunction "2_2") (pintype "passive"))
    )
    (net (code "41") (name "Net-(IC12-~{Q})") (class "Default")
      (node (ref "IC12") (pin "13") (pinfunction "~{Q}_13") (pintype "output"))
      (node (ref "R72") (pin "1") (pinfunction "1_1") (pintype "passive"))
    )
    (net (code "42") (name "Net-(IC13-IN+)") (class "Default")
      (node (ref "C59") (pin "2") (pinfunction "2_2") (pintype "passive"))
      (node (ref "IC13") (pin "3") (pinfunction "IN+_3") (pintype "input"))
      (node (ref "R74") (pin "1") (pinfunction "1_1") (pintype "passive"))
    )
    (net (code "43") (name "Net-(IC13-IN-)") (class "Default")
      (node (ref "IC13") (pin "4") (pinfunction "IN-_4") (pintype "input"))
      (node (ref "R67") (pin "2") (pinfunction "2_2") (pintype "passive"))
      (node (ref "R68") (pin "2") (pinfunction "2_2") (pintype "passive"))
    )
    (net (code "44") (name "Net-(IC13-OUT)") (class "Default")
      (node (ref "IC13") (pin "1") (pinfunction "OUT_1") (pintype "output"))
      (node (ref "R67") (pin "1") (pinfunction "1_1") (pintype "passive"))
      (node (ref "R70") (pin "1") (pinfunction "1_1") (pintype "passive"))
    )
    (net (code "45") (name "Net-(IC13-V+)") (class "Default")
      (node (ref "C57") (pin "2") (pinfunction "2_2") (pintype "passive"))
      (node (ref "IC13") (pin "5") (pinfunction "V+_5") (pintype "power_in"))
      (node (ref "L12") (pin "1") (pinfunction "1_1") (pintype "passive"))
    )
    (net (code "46") (name "Net-(J3-Pad1)") (class "Default")
      (node (ref "J3") (pin "1") (pinfunction "1_1") (pintype "bidirectional"))
      (node (ref "R50") (pin "1") (pinfunction "1_1") (pintype "passive"))
    )
    (net (code "47") (name "Net-(J4-Pad1)") (class "Default")
      (node (ref "J4") (pin "1") (pinfunction "1_1") (pintype "bidirectional"))
      (node (ref "R51") (pin "1") (pinfunction "1_1") (pintype "passive"))
    )
    (net (code "48") (name "Net-(P7-Pad5)") (class "Default")
      (node (ref "P7") (pin "5") (pinfunction "5_5") (pintype "passive"))
      (node (ref "R70") (pin "2") (pinfunction "2_2") (pintype "passive"))
    )
    (net (code "49") (name "P3V3A") (class "Default")
      (node (ref "C51") (pin "1") (pinfunction "1_1") (pintype "passive"))
      (node (ref "IC11") (pin "4") (pinfunction "OUT_4") (pintype "power_in"))
      (node (ref "L12") (pin "2") (pinfunction "2_2") (pintype "passive"))
      (node (ref "R62") (pin "2") (pinfunction "2_2") (pintype "passive"))
      (node (ref "R63") (pin "1") (pinfunction "1_1") (pintype "passive"))
    )
    (net (code "50") (name "P3V3ADL") (class "Default")
      (node (ref "C53") (pin "2") (pinfunction "2_2") (pintype "passive"))
      (node (ref "C54") (pin "2") (pinfunction "2_2") (pintype "passive"))
      (node (ref "C55") (pin "2") (pinfunction "2_2") (pintype "passive"))
      (node (ref "IC12") (pin "5") (pinfunction "VPOS_5") (pintype "power_in"))
      (node (ref "IC12") (pin "7") (pinfunction "VPOS_7") (pintype "power_in"))
      (node (ref "R63") (pin "2") (pinfunction "2_2") (pintype "passive"))
      (node (ref "R64") (pin "1") (pinfunction "1_1") (pintype "passive"))
    )
    (net (code "51") (name "VCC_PREAMP") (class "Default")
      (node (ref "L11") (pin "2") (pinfunction "2_2") (pintype "passive"))
      (node (ref "L8") (pin "1") (pinfunction "1_1") (pintype "passive"))
      (node (ref "P8") (pin "2") (pinfunction "2_2") (pintype "passive"))
    )
    (net (code "52") (name "VCC_PREAMP_1") (class "Default")
      (node (ref "C18") (pin "2") (pinfunction "2_2") (pintype "passive"))
      (node (ref "C52") (pin "2") (pinfunction "2_2") (pintype "passive"))
      (node (ref "IC11") (pin "3") (pinfunction "~{SD}_3") (pintype "input"))
      (node (ref "IC11") (pin "5") (pinfunction "IN_5") (pintype "input"))
      (node (ref "P7") (pin "8") (pinfunction "8_8") (pintype "passive"))
    )
    (net (code "53") (name "unconnected-(IC9-NU-Pad5)") (class "Default")
      (node (ref "IC9") (pin "5") (pinfunction "NU_5") (pintype "passive"))
    )
    (net (code "54") (name "unconnected-(IC11-NR-Pad2)") (class "Default")
      (node (ref "IC11") (pin "2") (pinfunction "NR_2") (pintype "input+no_connect"))
    )
    (net (code "55") (name "unconnected-(IC12-DNC-Pad2)") (class "Default")
      (node (ref "IC12") (pin "2") (pinfunction "DNC_2") (pintype "passive+no_connect"))
    )
    (net (code "56") (name "unconnected-(IC12-DNC-Pad6)") (class "Default")
      (node (ref "IC12") (pin "6") (pinfunction "DNC_6") (pintype "passive+no_connect"))
    )
    (net (code "57") (name "unconnected-(IC12-DNC-Pad8)") (class "Default")
      (node (ref "IC12") (pin "8") (pinfunction "DNC_8") (pintype "passive+no_connect"))
    )
    (net (code "58") (name "unconnected-(IC12-VCAL-Pad3)") (class "Default")
      (node (ref "IC12") (pin "3") (pinfunction "VCAL_3") (pintype "input+no_connect"))
    )
    (net (code "59") (name "unconnected-(P7-Pad2)") (class "Default")
      (node (ref "P7") (pin "2") (pinfunction "2_2") (pintype "passive+no_connect"))
    )
    (net (code "60") (name "unconnected-(P7-Pad4)") (class "Default")
      (node (ref "P7") (pin "4") (pinfunction "4_4") (pintype "passive+no_connect"))
    )
    (net (code "61") (name "unconnected-(P8-Pad3)") (class "Default")
      (node (ref "P8") (pin "3") (pinfunction "3_3") (pintype "passive+no_connect"))
    )
    (net (code "62") (name "unconnected-(P8-Pad4)") (class "Default")
      (node (ref "P8") (pin "4") (pinfunction "4_4") (pintype "passive+no_connect"))
    )
    (net (code "63") (name "unconnected-(P8-Pad5)") (class "Default")
      (node (ref "P8") (pin "5") (pinfunction "5_5") (pintype "passive+no_connect"))
    )
    (net (code "64") (name "unconnected-(P8-Pad6)") (class "Default")
      (node (ref "P8") (pin "6") (pinfunction "6_6") (pintype "passive+no_connect"))
    )
  )
)
